# SENSORS.net
KiCad netlist of a schematic drawn in Altium Designer
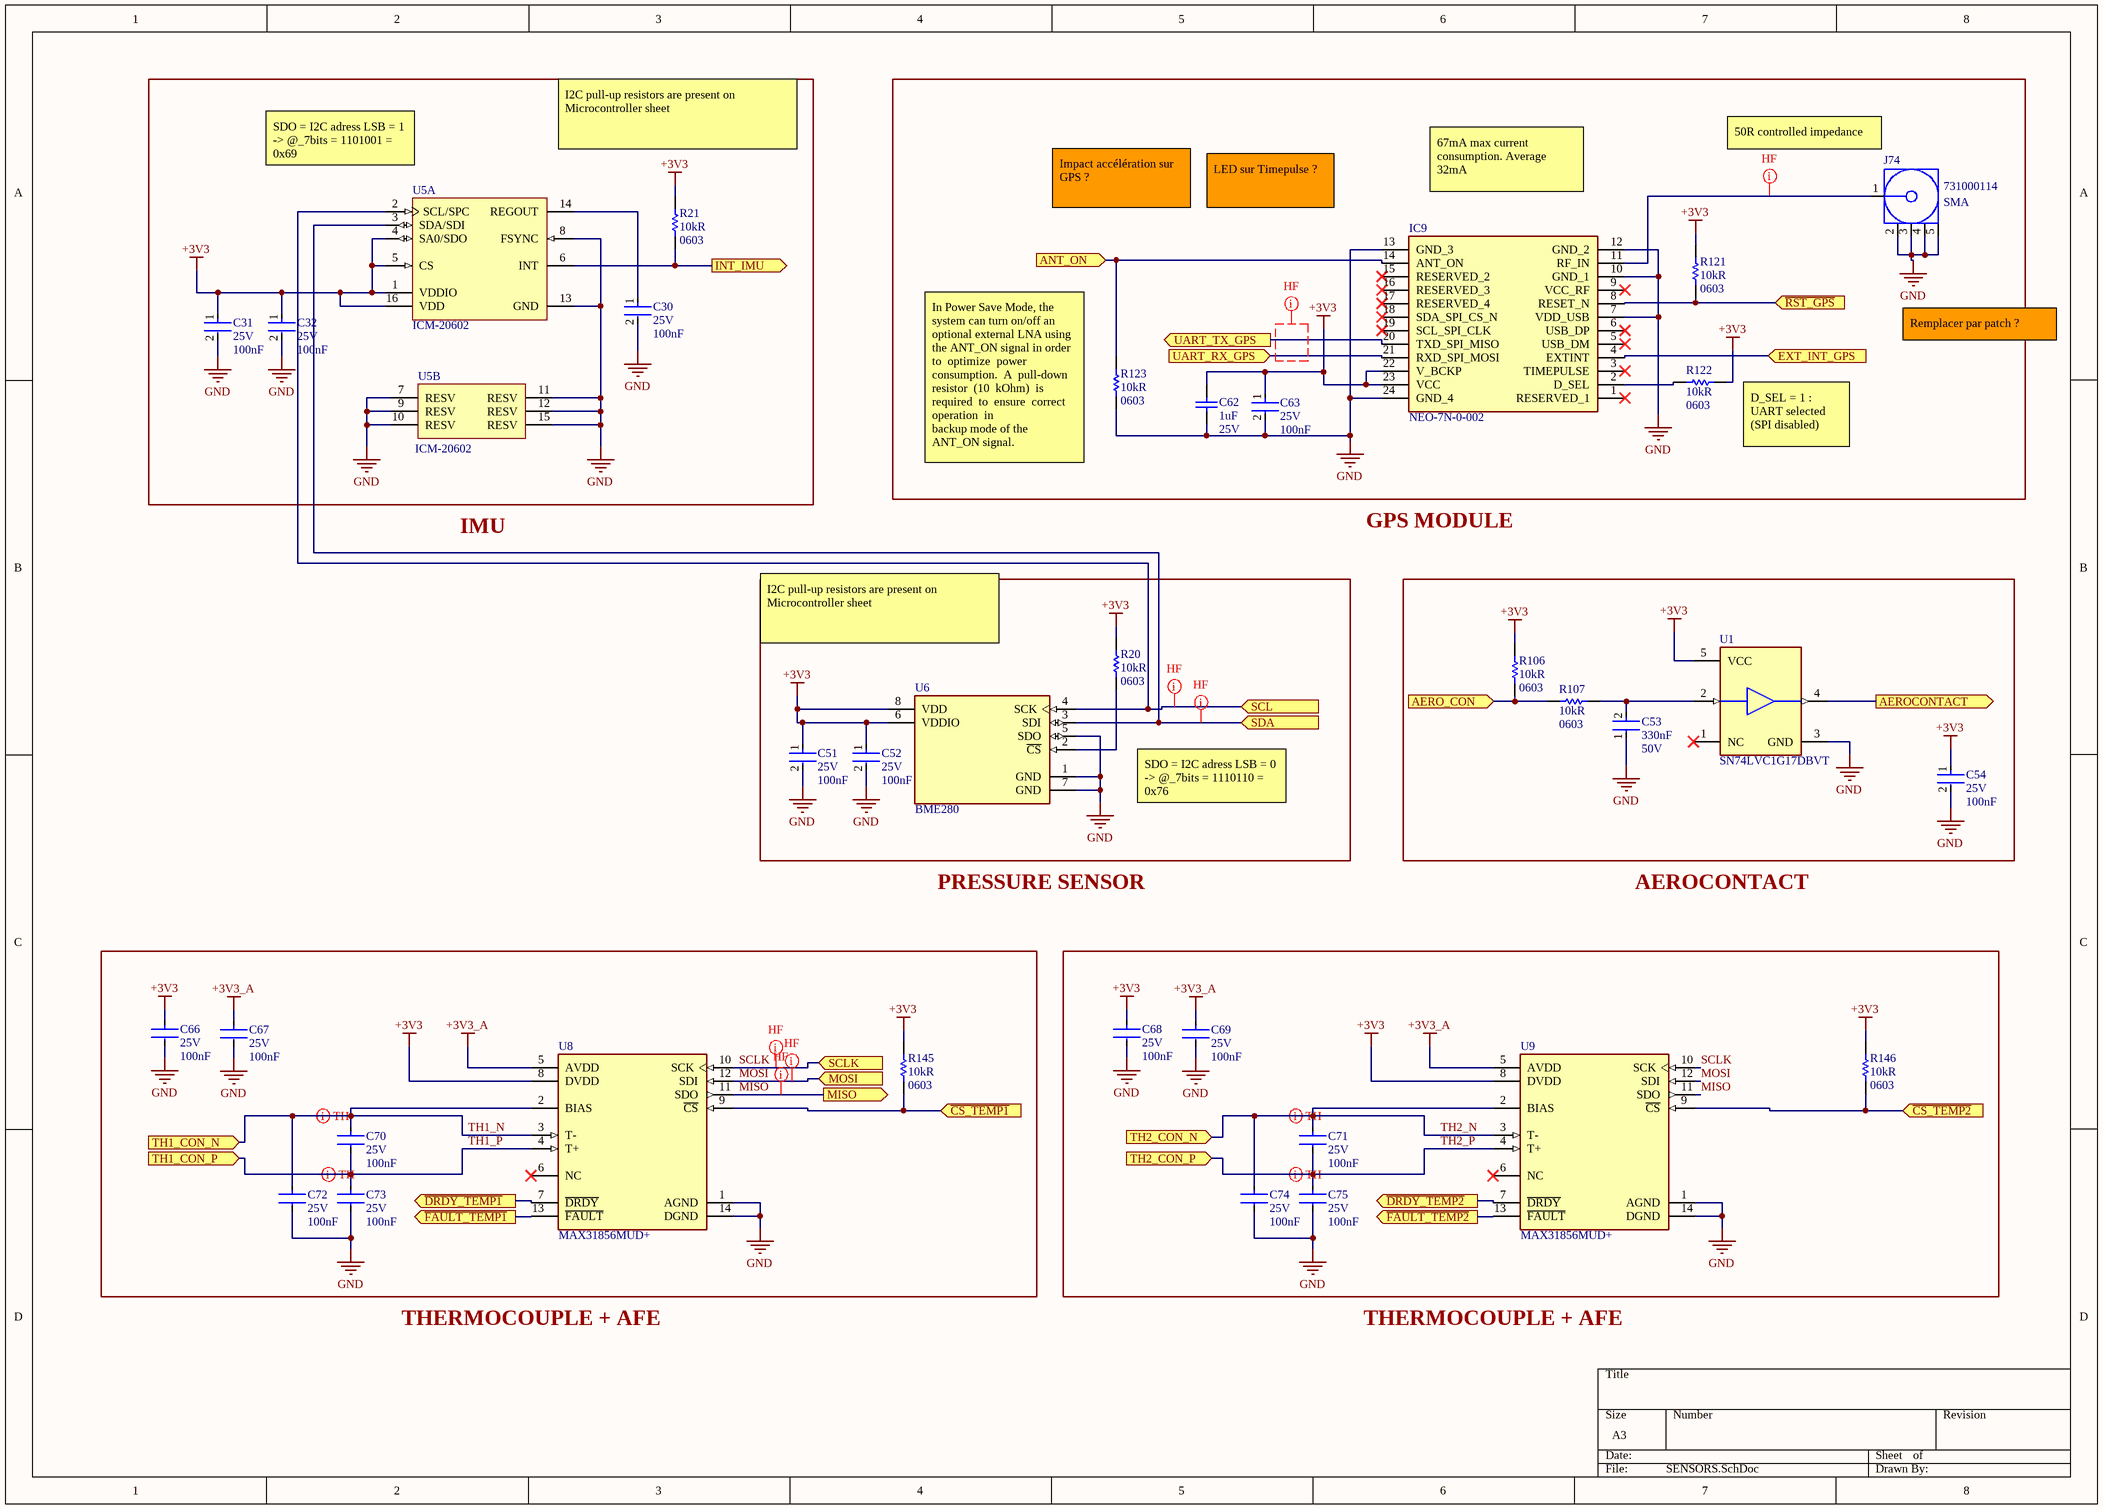
[diagram p0: SENSORS.SchDoc]

(export (version "E")
  (design (tool "Eeschema 10.0.6"))
  (components
    (comp (ref "C30")
      (value "CGA3E2X7R1E104K080AA")
      (footprint "FP-CGA3E-0_3-0_1-MFG")
      (description "Cap Ceramic 100nF 25V X7R 10% Pad SMD 0603 +125°C Automotive T/R")
      (fields
        (field (name "VOLTAGE RATING (DC)") "25V")
        (field (name "CAPACITANCE") "100nF")
        (field (name "TOLERANCE") "10%")
        (field (name "MANUFACTURER") "TDK")
      )
      (libsource (lib "Altium Content Vault") (part "b4654b650e69147ec39a6b967a45e02"))
    )
    (comp (ref "C31")
      (value "CGA3E2X7R1E104K080AA")
      (footprint "FP-CGA3E-0_3-0_1-MFG")
      (description "Cap Ceramic 100nF 25V X7R 10% Pad SMD 0603 +125°C Automotive T/R")
      (fields
        (field (name "VOLTAGE RATING (DC)") "25V")
        (field (name "CAPACITANCE") "100nF")
        (field (name "TOLERANCE") "10%")
        (field (name "MANUFACTURER") "TDK")
      )
      (libsource (lib "Altium Content Vault") (part "b4654b650e69147ec39a6b967a45e02"))
    )
    (comp (ref "C32")
      (value "CGA3E2X7R1E104K080AA")
      (footprint "FP-CGA3E-0_3-0_1-MFG")
      (description "Cap Ceramic 100nF 25V X7R 10% Pad SMD 0603 +125°C Automotive T/R")
      (fields
        (field (name "VOLTAGE RATING (DC)") "25V")
        (field (name "CAPACITANCE") "100nF")
        (field (name "TOLERANCE") "10%")
        (field (name "MANUFACTURER") "TDK")
      )
      (libsource (lib "Altium Content Vault") (part "b4654b650e69147ec39a6b967a45e02"))
    )
    (comp (ref "C51")
      (value "CGA3E2X7R1E104K080AA")
      (footprint "FP-CGA3E-0_3-0_1-MFG")
      (description "Cap Ceramic 100nF 25V X7R 10% Pad SMD 0603 +125°C Automotive T/R")
      (fields
        (field (name "VOLTAGE RATING (DC)") "25V")
        (field (name "CAPACITANCE") "100nF")
        (field (name "TOLERANCE") "10%")
        (field (name "MANUFACTURER") "TDK")
      )
      (libsource (lib "Altium Content Vault") (part "b4654b650e69147ec39a6b967a45e02"))
    )
    (comp (ref "C52")
      (value "CGA3E2X7R1E104K080AA")
      (footprint "FP-CGA3E-0_3-0_1-MFG")
      (description "Cap Ceramic 100nF 25V X7R 10% Pad SMD 0603 +125°C Automotive T/R")
      (fields
        (field (name "VOLTAGE RATING (DC)") "25V")
        (field (name "CAPACITANCE") "100nF")
        (field (name "TOLERANCE") "10%")
        (field (name "MANUFACTURER") "TDK")
      )
      (libsource (lib "Altium Content Vault") (part "b4654b650e69147ec39a6b967a45e02"))
    )
    (comp (ref "C53")
      (value "C1608X7R1H334K080AC")
      (footprint "FP-C1608-080-0_1-IPC_B")
      (description "Multilayer Ceramic Capacitors 330nF ±10% 50V X7R SMD 0603")
      (fields
        (field (name "CAPACITANCE") "330nF")
        (field (name "VOLTAGE RATING") "50V")
        (field (name "TOLERANCE") "10%")
        (field (name "VOLTAGE") "50V")
      )
      (libsource (lib "Altium Content Vault") (part "236180d848d6139a670b325ea6854c9"))
    )
    (comp (ref "C54")
      (value "CGA3E2X7R1E104K080AA")
      (footprint "FP-CGA3E-0_3-0_1-MFG")
      (description "Cap Ceramic 100nF 25V X7R 10% Pad SMD 0603 +125°C Automotive T/R")
      (fields
        (field (name "VOLTAGE RATING (DC)") "25V")
        (field (name "CAPACITANCE") "100nF")
        (field (name "TOLERANCE") "10%")
        (field (name "MANUFACTURER") "TDK")
      )
      (libsource (lib "Altium Content Vault") (part "b4654b650e69147ec39a6b967a45e02"))
    )
    (comp (ref "C62")
      (value "C0603C105K3PAC7867")
      (footprint "CAPC1608X90X35LL15T15")
      (fields
        (field (name "MANUFACTURER") "Kemet")
        (field (name "MANUFACTURER PART NUMBER") "C0603C105K3PACTU")
        (field (name "CAPACITANCE") "1uF")
        (field (name "TOLERANCE") "10%")
        (field (name "VOLTAGE RATING (DC)") "25V")
      )
      (libsource (lib "Altium Content Vault") (part "CAP"))
    )
    (comp (ref "C63")
      (value "CGA3E2X7R1E104K080AA")
      (footprint "FP-CGA3E-0_3-0_1-MFG")
      (description "Cap Ceramic 100nF 25V X7R 10% Pad SMD 0603 +125°C Automotive T/R")
      (fields
        (field (name "VOLTAGE RATING (DC)") "25V")
        (field (name "CAPACITANCE") "100nF")
        (field (name "TOLERANCE") "10%")
        (field (name "MANUFACTURER") "TDK")
      )
      (libsource (lib "Altium Content Vault") (part "b4654b650e69147ec39a6b967a45e02"))
    )
    (comp (ref "C66")
      (value "CGA3E2X7R1E104K080AA")
      (footprint "FP-CGA3E-0_3-0_1-MFG")
      (description "Cap Ceramic 100nF 25V X7R 10% Pad SMD 0603 +125°C Automotive T/R")
      (fields
        (field (name "VOLTAGE RATING (DC)") "25V")
        (field (name "CAPACITANCE") "100nF")
        (field (name "TOLERANCE") "10%")
        (field (name "MANUFACTURER") "TDK")
      )
      (libsource (lib "") (part "b4654b650e69147ec39a6b967a45e02_1"))
    )
    (comp (ref "C67")
      (value "CGA3E2X7R1E104K080AA")
      (footprint "FP-CGA3E-0_3-0_1-MFG")
      (description "Cap Ceramic 100nF 25V X7R 10% Pad SMD 0603 +125°C Automotive T/R")
      (fields
        (field (name "VOLTAGE RATING (DC)") "25V")
        (field (name "CAPACITANCE") "100nF")
        (field (name "TOLERANCE") "10%")
        (field (name "MANUFACTURER") "TDK")
      )
      (libsource (lib "") (part "b4654b650e69147ec39a6b967a45e02_1"))
    )
    (comp (ref "C68")
      (value "CGA3E2X7R1E104K080AA")
      (footprint "FP-CGA3E-0_3-0_1-MFG")
      (description "Cap Ceramic 100nF 25V X7R 10% Pad SMD 0603 +125°C Automotive T/R")
      (fields
        (field (name "VOLTAGE RATING (DC)") "25V")
        (field (name "CAPACITANCE") "100nF")
        (field (name "TOLERANCE") "10%")
        (field (name "MANUFACTURER") "TDK")
      )
      (libsource (lib "") (part "b4654b650e69147ec39a6b967a45e02_1"))
    )
    (comp (ref "C69")
      (value "CGA3E2X7R1E104K080AA")
      (footprint "FP-CGA3E-0_3-0_1-MFG")
      (description "Cap Ceramic 100nF 25V X7R 10% Pad SMD 0603 +125°C Automotive T/R")
      (fields
        (field (name "VOLTAGE RATING (DC)") "25V")
        (field (name "CAPACITANCE") "100nF")
        (field (name "TOLERANCE") "10%")
        (field (name "MANUFACTURER") "TDK")
      )
      (libsource (lib "") (part "b4654b650e69147ec39a6b967a45e02_1"))
    )
    (comp (ref "C70")
      (value "CGA3E2X7R1E104K080AA")
      (footprint "FP-CGA3E-0_3-0_1-MFG")
      (description "Cap Ceramic 100nF 25V X7R 10% Pad SMD 0603 +125°C Automotive T/R")
      (fields
        (field (name "VOLTAGE RATING (DC)") "25V")
        (field (name "CAPACITANCE") "100nF")
        (field (name "TOLERANCE") "10%")
        (field (name "MANUFACTURER") "TDK")
      )
      (libsource (lib "") (part "b4654b650e69147ec39a6b967a45e02_1"))
    )
    (comp (ref "C71")
      (value "CGA3E2X7R1E104K080AA")
      (footprint "FP-CGA3E-0_3-0_1-MFG")
      (description "Cap Ceramic 100nF 25V X7R 10% Pad SMD 0603 +125°C Automotive T/R")
      (fields
        (field (name "VOLTAGE RATING (DC)") "25V")
        (field (name "CAPACITANCE") "100nF")
        (field (name "TOLERANCE") "10%")
        (field (name "MANUFACTURER") "TDK")
      )
      (libsource (lib "") (part "b4654b650e69147ec39a6b967a45e02_1"))
    )
    (comp (ref "C72")
      (value "CGA3E2X7R1E104K080AA")
      (footprint "FP-CGA3E-0_3-0_1-MFG")
      (description "Cap Ceramic 100nF 25V X7R 10% Pad SMD 0603 +125°C Automotive T/R")
      (fields
        (field (name "VOLTAGE RATING (DC)") "25V")
        (field (name "CAPACITANCE") "100nF")
        (field (name "TOLERANCE") "10%")
        (field (name "MANUFACTURER") "TDK")
      )
      (libsource (lib "") (part "b4654b650e69147ec39a6b967a45e02_1"))
    )
    (comp (ref "C73")
      (value "CGA3E2X7R1E104K080AA")
      (footprint "FP-CGA3E-0_3-0_1-MFG")
      (description "Cap Ceramic 100nF 25V X7R 10% Pad SMD 0603 +125°C Automotive T/R")
      (fields
        (field (name "VOLTAGE RATING (DC)") "25V")
        (field (name "CAPACITANCE") "100nF")
        (field (name "TOLERANCE") "10%")
        (field (name "MANUFACTURER") "TDK")
      )
      (libsource (lib "") (part "b4654b650e69147ec39a6b967a45e02_1"))
    )
    (comp (ref "C74")
      (value "CGA3E2X7R1E104K080AA")
      (footprint "FP-CGA3E-0_3-0_1-MFG")
      (description "Cap Ceramic 100nF 25V X7R 10% Pad SMD 0603 +125°C Automotive T/R")
      (fields
        (field (name "VOLTAGE RATING (DC)") "25V")
        (field (name "CAPACITANCE") "100nF")
        (field (name "TOLERANCE") "10%")
        (field (name "MANUFACTURER") "TDK")
      )
      (libsource (lib "") (part "b4654b650e69147ec39a6b967a45e02_1"))
    )
    (comp (ref "C75")
      (value "CGA3E2X7R1E104K080AA")
      (footprint "FP-CGA3E-0_3-0_1-MFG")
      (description "Cap Ceramic 100nF 25V X7R 10% Pad SMD 0603 +125°C Automotive T/R")
      (fields
        (field (name "VOLTAGE RATING (DC)") "25V")
        (field (name "CAPACITANCE") "100nF")
        (field (name "TOLERANCE") "10%")
        (field (name "MANUFACTURER") "TDK")
      )
      (libsource (lib "") (part "b4654b650e69147ec39a6b967a45e02_1"))
    )
    (comp (ref "IC9")
      (value "NEO-7N-0-002")
      (footprint "SamacSys:NEO7N0002")
      (description "Integrated Circuit")
      (libsource (lib "*") (part "NEO-7N-0-002"))
    )
    (comp (ref "J74")
      (value "731000114")
      (footprint "MOLX-731000114_V")
      (description "SMA Right-Angle PCB Jack Receptacle, Brass Body, Gold Plated, 50 Ohm, 5-Pin THD, RoHS, Tray")
      (fields
        (field (name "MANUFACTURER") "Molex")
        (field (name "MANUFACTURER PART NUMBER") "73100-0114")
        (field (name "CASE/PACKAGE") "SMA")
      )
      (libsource (lib "Altium Content Vault") (part "CN-S-4F-RF5"))
    )
    (comp (ref "R20")
      (value "ERJ3EKF1002V")
      (footprint "RESC1609X55X30LL15T15")
      (description "Chip Resistor, 10 KOhm, +/- 1%, 0.1 W, -55 to 155 degC, 0603 (1608 Metric), RoHS, Tape and Reel")
      (fields
        (field (name "RESISTANCE") "10kR")
        (field (name "CASE CODE (IMPERIAL)") "0603")
        (field (name "TOLERANCE") "1%")
        (field (name "MANUFACTURER") "Panasonic")
      )
      (libsource (lib "Altium Content Vault") (part "RES-2"))
    )
    (comp (ref "R21")
      (value "ERJ3EKF1002V")
      (footprint "RESC1609X55X30LL15T15")
      (description "Chip Resistor, 10 KOhm, +/- 1%, 0.1 W, -55 to 155 degC, 0603 (1608 Metric), RoHS, Tape and Reel")
      (fields
        (field (name "RESISTANCE") "10kR")
        (field (name "CASE CODE (IMPERIAL)") "0603")
        (field (name "TOLERANCE") "1%")
        (field (name "MANUFACTURER") "Panasonic")
      )
      (libsource (lib "Altium Content Vault") (part "RES-2"))
    )
    (comp (ref "R106")
      (value "ERJ3EKF1002V")
      (footprint "RESC1609X55X30LL15T15")
      (description "Chip Resistor, 10 KOhm, +/- 1%, 0.1 W, -55 to 155 degC, 0603 (1608 Metric), RoHS, Tape and Reel")
      (fields
        (field (name "RESISTANCE") "10kR")
        (field (name "CASE CODE (IMPERIAL)") "0603")
        (field (name "TOLERANCE") "1%")
        (field (name "MANUFACTURER") "Panasonic")
      )
      (libsource (lib "Altium Content Vault") (part "RES-2"))
    )
    (comp (ref "R107")
      (value "ERJ3EKF1002V")
      (footprint "RESC1609X55X30LL15T15")
      (description "Chip Resistor, 10 KOhm, +/- 1%, 0.1 W, -55 to 155 degC, 0603 (1608 Metric), RoHS, Tape and Reel")
      (fields
        (field (name "RESISTANCE") "10kR")
        (field (name "CASE CODE (IMPERIAL)") "0603")
        (field (name "TOLERANCE") "1%")
        (field (name "MANUFACTURER") "Panasonic")
      )
      (libsource (lib "Altium Content Vault") (part "RES-2"))
    )
    (comp (ref "R121")
      (value "ERJ3EKF1002V")
      (footprint "RESC1609X55X30LL15T15")
      (description "Chip Resistor, 10 KOhm, +/- 1%, 0.1 W, -55 to 155 degC, 0603 (1608 Metric), RoHS, Tape and Reel")
      (fields
        (field (name "RESISTANCE") "10kR")
        (field (name "CASE CODE (IMPERIAL)") "0603")
        (field (name "TOLERANCE") "1%")
        (field (name "MANUFACTURER") "Panasonic")
      )
      (libsource (lib "Altium Content Vault") (part "RES-2"))
    )
    (comp (ref "R122")
      (value "ERJ3EKF1002V")
      (footprint "RESC1609X55X30LL15T15")
      (description "Chip Resistor, 10 KOhm, +/- 1%, 0.1 W, -55 to 155 degC, 0603 (1608 Metric), RoHS, Tape and Reel")
      (fields
        (field (name "RESISTANCE") "10kR")
        (field (name "CASE CODE (IMPERIAL)") "0603")
        (field (name "TOLERANCE") "1%")
        (field (name "MANUFACTURER") "Panasonic")
      )
      (libsource (lib "Altium Content Vault") (part "RES-2"))
    )
    (comp (ref "R123")
      (value "ERJ3EKF1002V")
      (footprint "RESC1609X55X30LL15T15")
      (description "Chip Resistor, 10 KOhm, +/- 1%, 0.1 W, -55 to 155 degC, 0603 (1608 Metric), RoHS, Tape and Reel")
      (fields
        (field (name "RESISTANCE") "10kR")
        (field (name "CASE CODE (IMPERIAL)") "0603")
        (field (name "TOLERANCE") "1%")
        (field (name "MANUFACTURER") "Panasonic")
      )
      (libsource (lib "Altium Content Vault") (part "RES-2"))
    )
    (comp (ref "R145")
      (value "ERJ3EKF1002V")
      (footprint "RESC1609X55X30LL15T15")
      (description "Chip Resistor, 10 KOhm, +/- 1%, 0.1 W, -55 to 155 degC, 0603 (1608 Metric), RoHS, Tape and Reel")
      (fields
        (field (name "RESISTANCE") "10kR")
        (field (name "CASE CODE (IMPERIAL)") "0603")
        (field (name "TOLERANCE") "1%")
        (field (name "MANUFACTURER") "Panasonic")
      )
      (libsource (lib "Altium Content Vault") (part "RES-2"))
    )
    (comp (ref "R146")
      (value "ERJ3EKF1002V")
      (footprint "RESC1609X55X30LL15T15")
      (description "Chip Resistor, 10 KOhm, +/- 1%, 0.1 W, -55 to 155 degC, 0603 (1608 Metric), RoHS, Tape and Reel")
      (fields
        (field (name "RESISTANCE") "10kR")
        (field (name "CASE CODE (IMPERIAL)") "0603")
        (field (name "TOLERANCE") "1%")
        (field (name "MANUFACTURER") "Panasonic")
      )
      (libsource (lib "Altium Content Vault") (part "RES-2"))
    )
    (comp (ref "U1")
      (value "SN74LVC1G17DBVT")
      (footprint "FP-DBV0005A-MFG")
      (description "IC BUF NON-INVERT 5.5V SOT23-5")
      (fields
        (field (name "MANUFACTURER") "Texas Instruments")
        (field (name "OCTOPART") "https://octopart.com/sn74lvc1g17dbvt-texas+instruments-2326350")
      )
      (libsource (lib "Altium Content Vault") (part "d67d855942c6c6b24b3bb5c51ad1e18"))
    )
    (comp (ref "U5")
      (value "ICM-20602")
      (footprint "INSE-I62-16")
      (fields (field (name "MANUFACTURER") "InvenSense"))
      (libsource (lib "Altium Content Vault") (part "INSE-ICM-20602-16"))
    )
    (comp (ref "U6")
      (value "BME280")
      (footprint "FP-BME280-MFG")
      (description "SENSOR PRESSURE HUMIDITY TEMP")
      (libsource (lib "Altium Content Vault") (part "d58e2f6669bc67e6a2bc6a28610ca79"))
    )
    (comp (ref "U8")
      (value "MAX31856MUD+")
      (footprint "FP-U14-2-MFG")
      (description "IC CONV THERMOCOUPLE 14TSSOP")
      (libsource (lib "Altium Content Vault") (part "746ee3d58a922cadd982a8de1b076a0"))
    )
    (comp (ref "U9")
      (value "MAX31856MUD+")
      (footprint "FP-U14-2-MFG")
      (description "IC CONV THERMOCOUPLE 14TSSOP")
      (libsource (lib "Altium Content Vault") (part "746ee3d58a922cadd982a8de1b076a0"))
    )
  )
  (nets
    (net (code "1") (name "+3V3") (class "Default")
      (node (ref "C31") (pin "1") (pinfunction "1_1") (pintype "passive"))
      (node (ref "C32") (pin "1") (pinfunction "1_1") (pintype "passive"))
      (node (ref "C51") (pin "1") (pinfunction "1_1") (pintype "passive"))
      (node (ref "C52") (pin "1") (pinfunction "1_1") (pintype "passive"))
      (node (ref "C54") (pin "1") (pinfunction "1_1") (pintype "passive"))
      (node (ref "C62") (pin "2") (pinfunction "2_2") (pintype "passive"))
      (node (ref "C63") (pin "1") (pinfunction "1_1") (pintype "passive"))
      (node (ref "C66") (pin "1") (pinfunction "1_1") (pintype "passive"))
      (node (ref "C68") (pin "1") (pinfunction "1_1") (pintype "passive"))
      (node (ref "IC9") (pin "22") (pinfunction "V_BCKP_22") (pintype "passive"))
      (node (ref "IC9") (pin "23") (pinfunction "VCC_23") (pintype "passive"))
      (node (ref "R106") (pin "2") (pinfunction "2_2") (pintype "passive"))
      (node (ref "R121") (pin "2") (pinfunction "2_2") (pintype "passive"))
      (node (ref "R122") (pin "2") (pinfunction "2_2") (pintype "passive"))
      (node (ref "R145") (pin "2") (pinfunction "2_2") (pintype "passive"))
      (node (ref "R146") (pin "2") (pinfunction "2_2") (pintype "passive"))
      (node (ref "R20") (pin "2") (pinfunction "2_2") (pintype "passive"))
      (node (ref "R21") (pin "2") (pinfunction "2_2") (pintype "passive"))
      (node (ref "U1") (pin "5") (pinfunction "VCC_5") (pintype "power_in"))
      (node (ref "U5") (pin "1") (pinfunction "VDDIO_1") (pintype "power_in"))
      (node (ref "U5") (pin "16") (pinfunction "VDD_16") (pintype "power_in"))
      (node (ref "U5") (pin "4") (pinfunction "SA0/SDO_4") (pintype "bidirectional"))
      (node (ref "U5") (pin "5") (pinfunction "CS_5") (pintype "input"))
      (node (ref "U6") (pin "6") (pinfunction "VDDIO_6") (pintype "power_in"))
      (node (ref "U6") (pin "8") (pinfunction "VDD_8") (pintype "power_in"))
      (node (ref "U8") (pin "8") (pinfunction "DVDD_8") (pintype "power_in"))
      (node (ref "U9") (pin "8") (pinfunction "DVDD_8") (pintype "power_in"))
    )
    (net (code "2") (name "+3V3_A") (class "Default")
      (node (ref "C67") (pin "1") (pinfunction "1_1") (pintype "passive"))
      (node (ref "C69") (pin "1") (pinfunction "1_1") (pintype "passive"))
      (node (ref "U8") (pin "5") (pinfunction "AVDD_5") (pintype "power_in"))
      (node (ref "U9") (pin "5") (pinfunction "AVDD_5") (pintype "power_in"))
    )
    (net (code "3") (name "/AEROCONTACT") (class "Default")
      (node (ref "U1") (pin "4") (pinfunction "Y_4") (pintype "output"))
    )
    (net (code "4") (name "/AERO_CON") (class "Default")
      (node (ref "R106") (pin "1") (pinfunction "1_1") (pintype "passive"))
      (node (ref "R107") (pin "2") (pinfunction "2_2") (pintype "passive"))
    )
    (net (code "5") (name "/ANT_ON") (class "Default")
      (node (ref "IC9") (pin "14") (pinfunction "ANT_ON_14") (pintype "passive"))
      (node (ref "R123") (pin "2") (pinfunction "2_2") (pintype "passive"))
    )
    (net (code "6") (name "/CS_TEMP1") (class "Default")
      (node (ref "R145") (pin "1") (pinfunction "1_1") (pintype "passive"))
      (node (ref "U8") (pin "9") (pinfunction "~{CS}_9") (pintype "input"))
    )
    (net (code "7") (name "/CS_TEMP2") (class "Default")
      (node (ref "R146") (pin "1") (pinfunction "1_1") (pintype "passive"))
      (node (ref "U9") (pin "9") (pinfunction "~{CS}_9") (pintype "input"))
    )
    (net (code "8") (name "/DRDY_TEMP1") (class "Default")
      (node (ref "U8") (pin "7") (pinfunction "~{DRDY}_7") (pintype "passive"))
    )
    (net (code "9") (name "/DRDY_TEMP2") (class "Default")
      (node (ref "U9") (pin "7") (pinfunction "~{DRDY}_7") (pintype "passive"))
    )
    (net (code "10") (name "/EXT_INT_GPS") (class "Default")
      (node (ref "IC9") (pin "4") (pinfunction "EXTINT_4") (pintype "passive"))
    )
    (net (code "11") (name "/FAULT_TEMP1") (class "Default")
      (node (ref "U8") (pin "13") (pinfunction "~{FAULT}_13") (pintype "passive"))
    )
    (net (code "12") (name "/FAULT_TEMP2") (class "Default")
      (node (ref "U9") (pin "13") (pinfunction "~{FAULT}_13") (pintype "passive"))
    )
    (net (code "13") (name "/INT_IMU") (class "Default")
      (node (ref "R21") (pin "1") (pinfunction "1_1") (pintype "passive"))
      (node (ref "U5") (pin "6") (pinfunction "INT_6") (pintype "open_collector"))
    )
    (net (code "14") (name "/MISO") (class "Default")
      (node (ref "U8") (pin "11") (pinfunction "SDO_11") (pintype "output"))
      (node (ref "U9") (pin "11") (pinfunction "SDO_11") (pintype "output"))
    )
    (net (code "15") (name "/MOSI") (class "Default")
      (node (ref "U8") (pin "12") (pinfunction "SDI_12") (pintype "input"))
      (node (ref "U9") (pin "12") (pinfunction "SDI_12") (pintype "input"))
    )
    (net (code "16") (name "/RST_GPS") (class "Default")
      (node (ref "IC9") (pin "8") (pinfunction "RESET_N_8") (pintype "passive"))
      (node (ref "R121") (pin "1") (pinfunction "1_1") (pintype "passive"))
    )
    (net (code "17") (name "/SCL") (class "Default")
      (node (ref "U5") (pin "2") (pinfunction "SCL/SPC_2") (pintype "input"))
      (node (ref "U6") (pin "4") (pinfunction "SCK_4") (pintype "input"))
    )
    (net (code "18") (name "/SCLK") (class "Default")
      (node (ref "U8") (pin "10") (pinfunction "SCK_10") (pintype "input"))
      (node (ref "U9") (pin "10") (pinfunction "SCK_10") (pintype "input"))
    )
    (net (code "19") (name "/SDA") (class "Default")
      (node (ref "U5") (pin "3") (pinfunction "SDA/SDI_3") (pintype "bidirectional"))
      (node (ref "U6") (pin "3") (pinfunction "SDI_3") (pintype "bidirectional"))
    )
    (net (code "20") (name "/TH1_N") (class "Default")
      (node (ref "C70") (pin "1") (pinfunction "1_1") (pintype "passive"))
      (node (ref "C72") (pin "1") (pinfunction "1_1") (pintype "passive"))
      (node (ref "U8") (pin "2") (pinfunction "BIAS_2") (pintype "passive"))
      (node (ref "U8") (pin "3") (pinfunction "T-_3") (pintype "input"))
    )
    (net (code "21") (name "/TH1_P") (class "Default")
      (node (ref "C70") (pin "2") (pinfunction "2_2") (pintype "passive"))
      (node (ref "C73") (pin "1") (pinfunction "1_1") (pintype "passive"))
      (node (ref "U8") (pin "4") (pinfunction "T+_4") (pintype "input"))
    )
    (net (code "22") (name "/TH2_N") (class "Default")
      (node (ref "C71") (pin "1") (pinfunction "1_1") (pintype "passive"))
      (node (ref "C74") (pin "1") (pinfunction "1_1") (pintype "passive"))
      (node (ref "U9") (pin "2") (pinfunction "BIAS_2") (pintype "passive"))
      (node (ref "U9") (pin "3") (pinfunction "T-_3") (pintype "input"))
    )
    (net (code "23") (name "/TH2_P") (class "Default")
      (node (ref "C71") (pin "2") (pinfunction "2_2") (pintype "passive"))
      (node (ref "C75") (pin "1") (pinfunction "1_1") (pintype "passive"))
      (node (ref "U9") (pin "4") (pinfunction "T+_4") (pintype "input"))
    )
    (net (code "24") (name "/UART_RX_GPS") (class "Default")
      (node (ref "IC9") (pin "21") (pinfunction "RXD_SPI_MOSI_21") (pintype "passive"))
    )
    (net (code "25") (name "/UART_TX_GPS") (class "Default")
      (node (ref "IC9") (pin "20") (pinfunction "TXD_SPI_MISO_20") (pintype "passive"))
    )
    (net (code "26") (name "GND") (class "Default")
      (node (ref "C30") (pin "2") (pinfunction "2_2") (pintype "passive"))
      (node (ref "C31") (pin "2") (pinfunction "2_2") (pintype "passive"))
      (node (ref "C32") (pin "2") (pinfunction "2_2") (pintype "passive"))
      (node (ref "C51") (pin "2") (pinfunction "2_2") (pintype "passive"))
      (node (ref "C52") (pin "2") (pinfunction "2_2") (pintype "passive"))
      (node (ref "C53") (pin "1") (pinfunction "1_1") (pintype "passive"))
      (node (ref "C54") (pin "2") (pinfunction "2_2") (pintype "passive"))
      (node (ref "C62") (pin "1") (pinfunction "1_1") (pintype "passive"))
      (node (ref "C63") (pin "2") (pinfunction "2_2") (pintype "passive"))
      (node (ref "C66") (pin "2") (pinfunction "2_2") (pintype "passive"))
      (node (ref "C67") (pin "2") (pinfunction "2_2") (pintype "passive"))
      (node (ref "C68") (pin "2") (pinfunction "2_2") (pintype "passive"))
      (node (ref "C69") (pin "2") (pinfunction "2_2") (pintype "passive"))
      (node (ref "C72") (pin "2") (pinfunction "2_2") (pintype "passive"))
      (node (ref "C73") (pin "2") (pinfunction "2_2") (pintype "passive"))
      (node (ref "C74") (pin "2") (pinfunction "2_2") (pintype "passive"))
      (node (ref "C75") (pin "2") (pinfunction "2_2") (pintype "passive"))
      (node (ref "IC9") (pin "10") (pinfunction "GND_1_10") (pintype "passive"))
      (node (ref "IC9") (pin "12") (pinfunction "GND_2_12") (pintype "passive"))
      (node (ref "IC9") (pin "13") (pinfunction "GND_3_13") (pintype "passive"))
      (node (ref "IC9") (pin "24") (pinfunction "GND_4_24") (pintype "passive"))
      (node (ref "IC9") (pin "7") (pinfunction "VDD_USB_7") (pintype "passive"))
      (node (ref "J74") (pin "2") (pinfunction "2_2") (pintype "passive"))
      (node (ref "J74") (pin "3") (pinfunction "3_3") (pintype "passive"))
      (node (ref "J74") (pin "4") (pinfunction "4_4") (pintype "passive"))
      (node (ref "J74") (pin "5") (pinfunction "5_5") (pintype "passive"))
      (node (ref "R123") (pin "1") (pinfunction "1_1") (pintype "passive"))
      (node (ref "U1") (pin "3") (pinfunction "GND_3") (pintype "power_in"))
      (node (ref "U5") (pin "10") (pinfunction "RESV_10") (pintype "passive"))
      (node (ref "U5") (pin "11") (pinfunction "RESV_11") (pintype "passive"))
      (node (ref "U5") (pin "12") (pinfunction "RESV_12") (pintype "passive"))
      (node (ref "U5") (pin "13") (pinfunction "GND_13") (pintype "power_in"))
      (node (ref "U5") (pin "15") (pinfunction "RESV_15") (pintype "passive"))
      (node (ref "U5") (pin "7") (pinfunction "RESV_7") (pintype "passive"))
      (node (ref "U5") (pin "8") (pinfunction "FSYNC_8") (pintype "input"))
      (node (ref "U5") (pin "9") (pinfunction "RESV_9") (pintype "passive"))
      (node (ref "U6") (pin "1") (pinfunction "GND_1") (pintype "power_in"))
      (node (ref "U6") (pin "5") (pinfunction "SDO_5") (pintype "bidirectional"))
      (node (ref "U6") (pin "7") (pinfunction "GND_7") (pintype "power_in"))
      (node (ref "U8") (pin "1") (pinfunction "AGND_1") (pintype "power_in"))
      (node (ref "U8") (pin "14") (pinfunction "DGND_14") (pintype "power_in"))
      (node (ref "U9") (pin "1") (pinfunction "AGND_1") (pintype "power_in"))
      (node (ref "U9") (pin "14") (pinfunction "DGND_14") (pintype "power_in"))
    )
    (net (code "27") (name "Net-(IC9-D_SEL)") (class "Default")
      (node (ref "IC9") (pin "2") (pinfunction "D_SEL_2") (pintype "passive"))
      (node (ref "R122") (pin "1") (pinfunction "1_1") (pintype "passive"))
    )
    (net (code "28") (name "Net-(IC9-RF_IN)") (class "Default")
      (node (ref "IC9") (pin "11") (pinfunction "RF_IN_11") (pintype "passive"))
      (node (ref "J74") (pin "1") (pinfunction "1_1") (pintype "passive"))
    )
    (net (code "29") (name "Net-(U1-A)") (class "Default")
      (node (ref "C53") (pin "2") (pinfunction "2_2") (pintype "passive"))
      (node (ref "R107") (pin "1") (pinfunction "1_1") (pintype "passive"))
      (node (ref "U1") (pin "2") (pinfunction "A_2") (pintype "input"))
    )
    (net (code "30") (name "Net-(U5A-REGOUT)") (class "Default")
      (node (ref "C30") (pin "1") (pinfunction "1_1") (pintype "passive"))
      (node (ref "U5") (pin "14") (pinfunction "REGOUT_14") (pintype "passive"))
    )
    (net (code "31") (name "Net-(U6-~{CS})") (class "Default")
      (node (ref "R20") (pin "1") (pinfunction "1_1") (pintype "passive"))
      (node (ref "U6") (pin "2") (pinfunction "~{CS}_2") (pintype "input"))
    )
    (net (code "32") (name "unconnected-(IC9-RESERVED_1-Pad1)") (class "Default")
      (node (ref "IC9") (pin "1") (pinfunction "RESERVED_1_1") (pintype "passive+no_connect"))
    )
    (net (code "33") (name "unconnected-(IC9-RESERVED_2-Pad15)") (class "Default")
      (node (ref "IC9") (pin "15") (pinfunction "RESERVED_2_15") (pintype "passive+no_connect"))
    )
    (net (code "34") (name "unconnected-(IC9-RESERVED_3-Pad16)") (class "Default")
      (node (ref "IC9") (pin "16") (pinfunction "RESERVED_3_16") (pintype "passive+no_connect"))
    )
    (net (code "35") (name "unconnected-(IC9-RESERVED_4-Pad17)") (class "Default")
      (node (ref "IC9") (pin "17") (pinfunction "RESERVED_4_17") (pintype "passive+no_connect"))
    )
    (net (code "36") (name "unconnected-(IC9-SCL_SPI_CLK-Pad19)") (class "Default")
      (node (ref "IC9") (pin "19") (pinfunction "SCL_SPI_CLK_19") (pintype "passive+no_connect"))
    )
    (net (code "37") (name "unconnected-(IC9-SDA_SPI_CS_N-Pad18)") (class "Default")
      (node (ref "IC9") (pin "18") (pinfunction "SDA_SPI_CS_N_18") (pintype "passive+no_connect"))
    )
    (net (code "38") (name "unconnected-(IC9-TIMEPULSE-Pad3)") (class "Default")
      (node (ref "IC9") (pin "3") (pinfunction "TIMEPULSE_3") (pintype "passive+no_connect"))
    )
    (net (code "39") (name "unconnected-(IC9-USB_DM-Pad5)") (class "Default")
      (node (ref "IC9") (pin "5") (pinfunction "USB_DM_5") (pintype "passive+no_connect"))
    )
    (net (code "40") (name "unconnected-(IC9-USB_DP-Pad6)") (class "Default")
      (node (ref "IC9") (pin "6") (pinfunction "USB_DP_6") (pintype "passive+no_connect"))
    )
    (net (code "41") (name "unconnected-(IC9-VCC_RF-Pad9)") (class "Default")
      (node (ref "IC9") (pin "9") (pinfunction "VCC_RF_9") (pintype "passive+no_connect"))
    )
    (net (code "42") (name "unconnected-(U1-NC-Pad1)") (class "Default")
      (node (ref "U1") (pin "1") (pinfunction "NC_1") (pintype "passive+no_connect"))
    )
    (net (code "43") (name "unconnected-(U8-NC-Pad6)") (class "Default")
      (node (ref "U8") (pin "6") (pinfunction "NC_6") (pintype "passive+no_connect"))
    )
    (net (code "44") (name "unconnected-(U9-NC-Pad6)") (class "Default")
      (node (ref "U9") (pin "6") (pinfunction "NC_6") (pintype "passive+no_connect"))
    )
  )
)
